# FPGA_DDR3_IO.net
KiCad netlist of a schematic drawn in Altium Designer
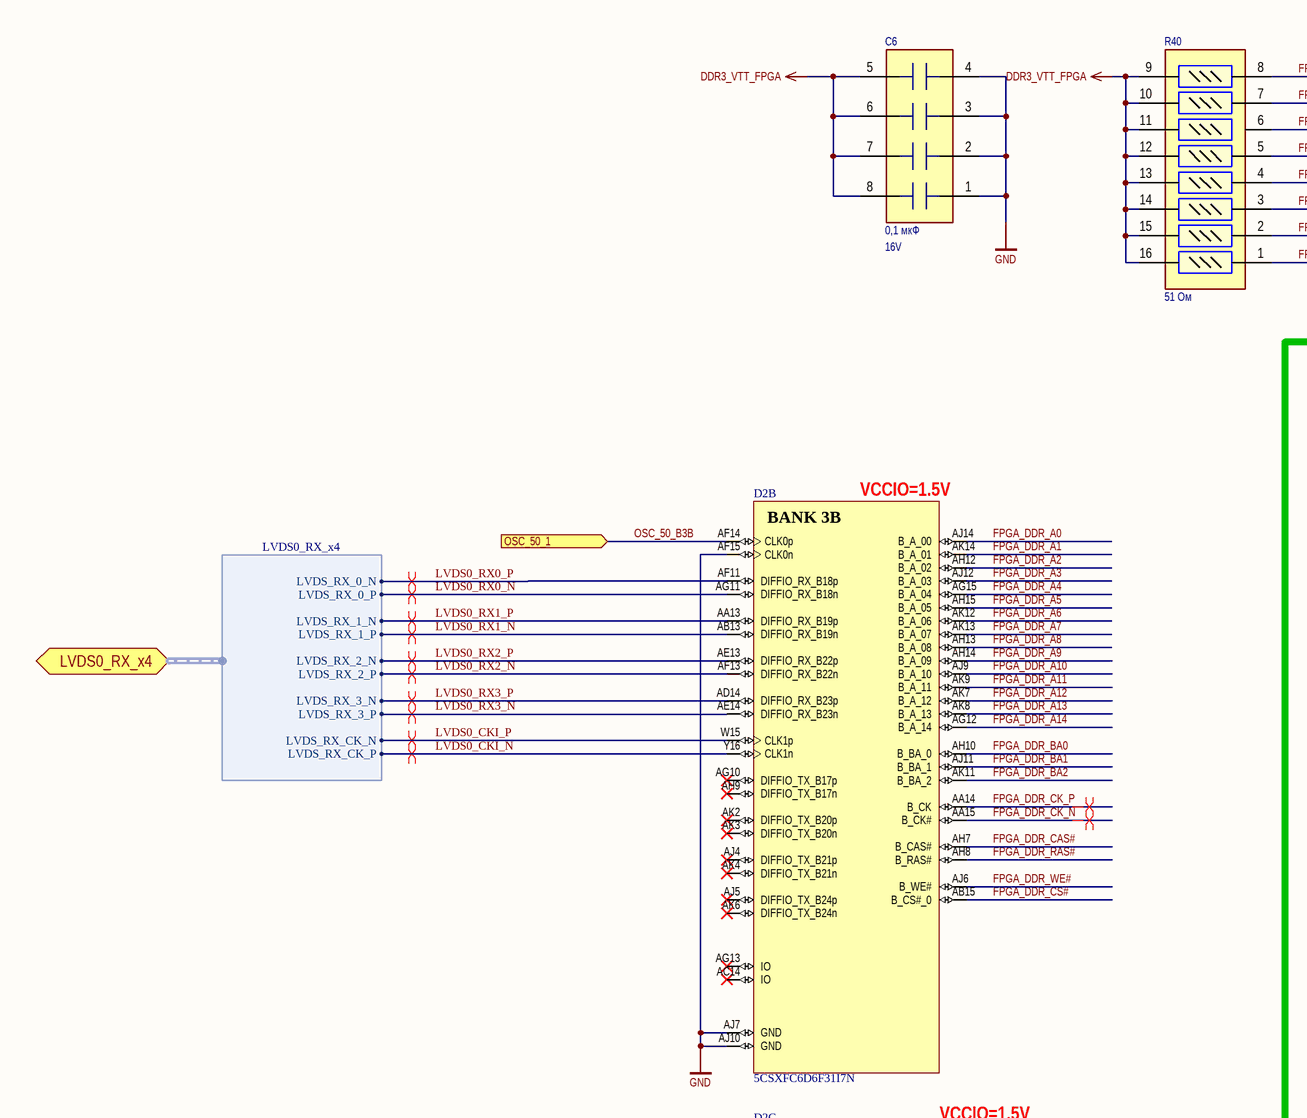
[diagram p0: FPGA_DDR3&IO.SchDoc, top left]
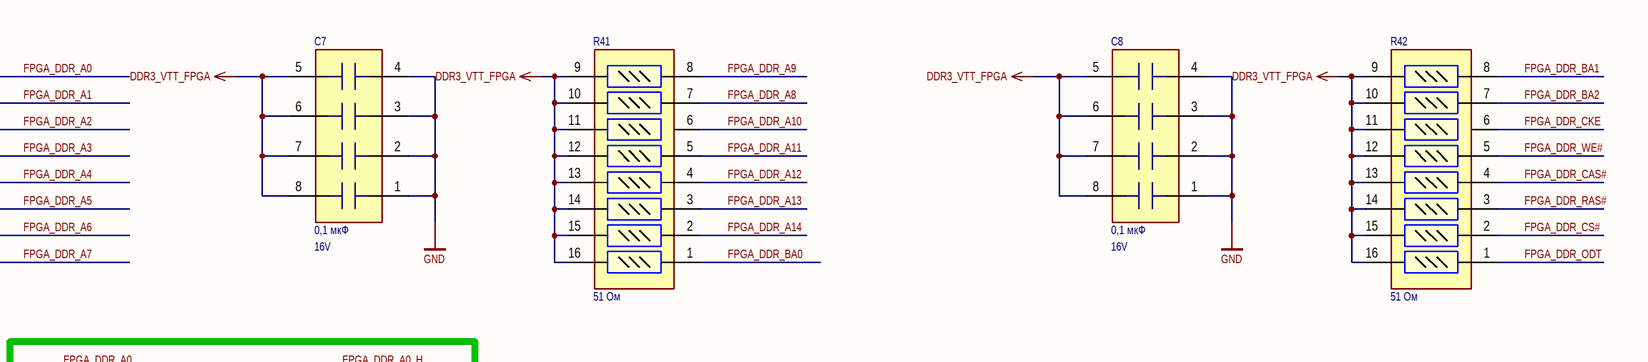
[diagram p1: FPGA_DDR3&IO.SchDoc, top right]
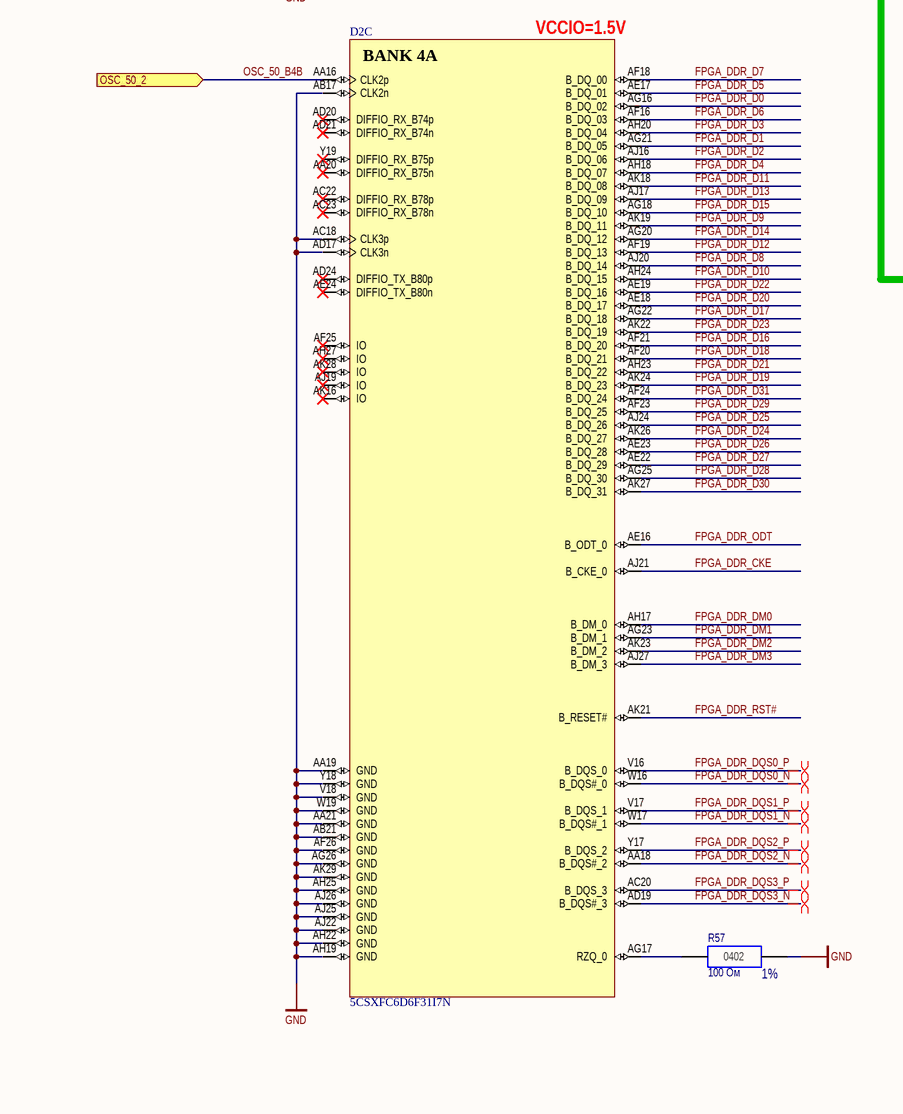
[diagram p2: FPGA_DDR3&IO.SchDoc, bottom left]
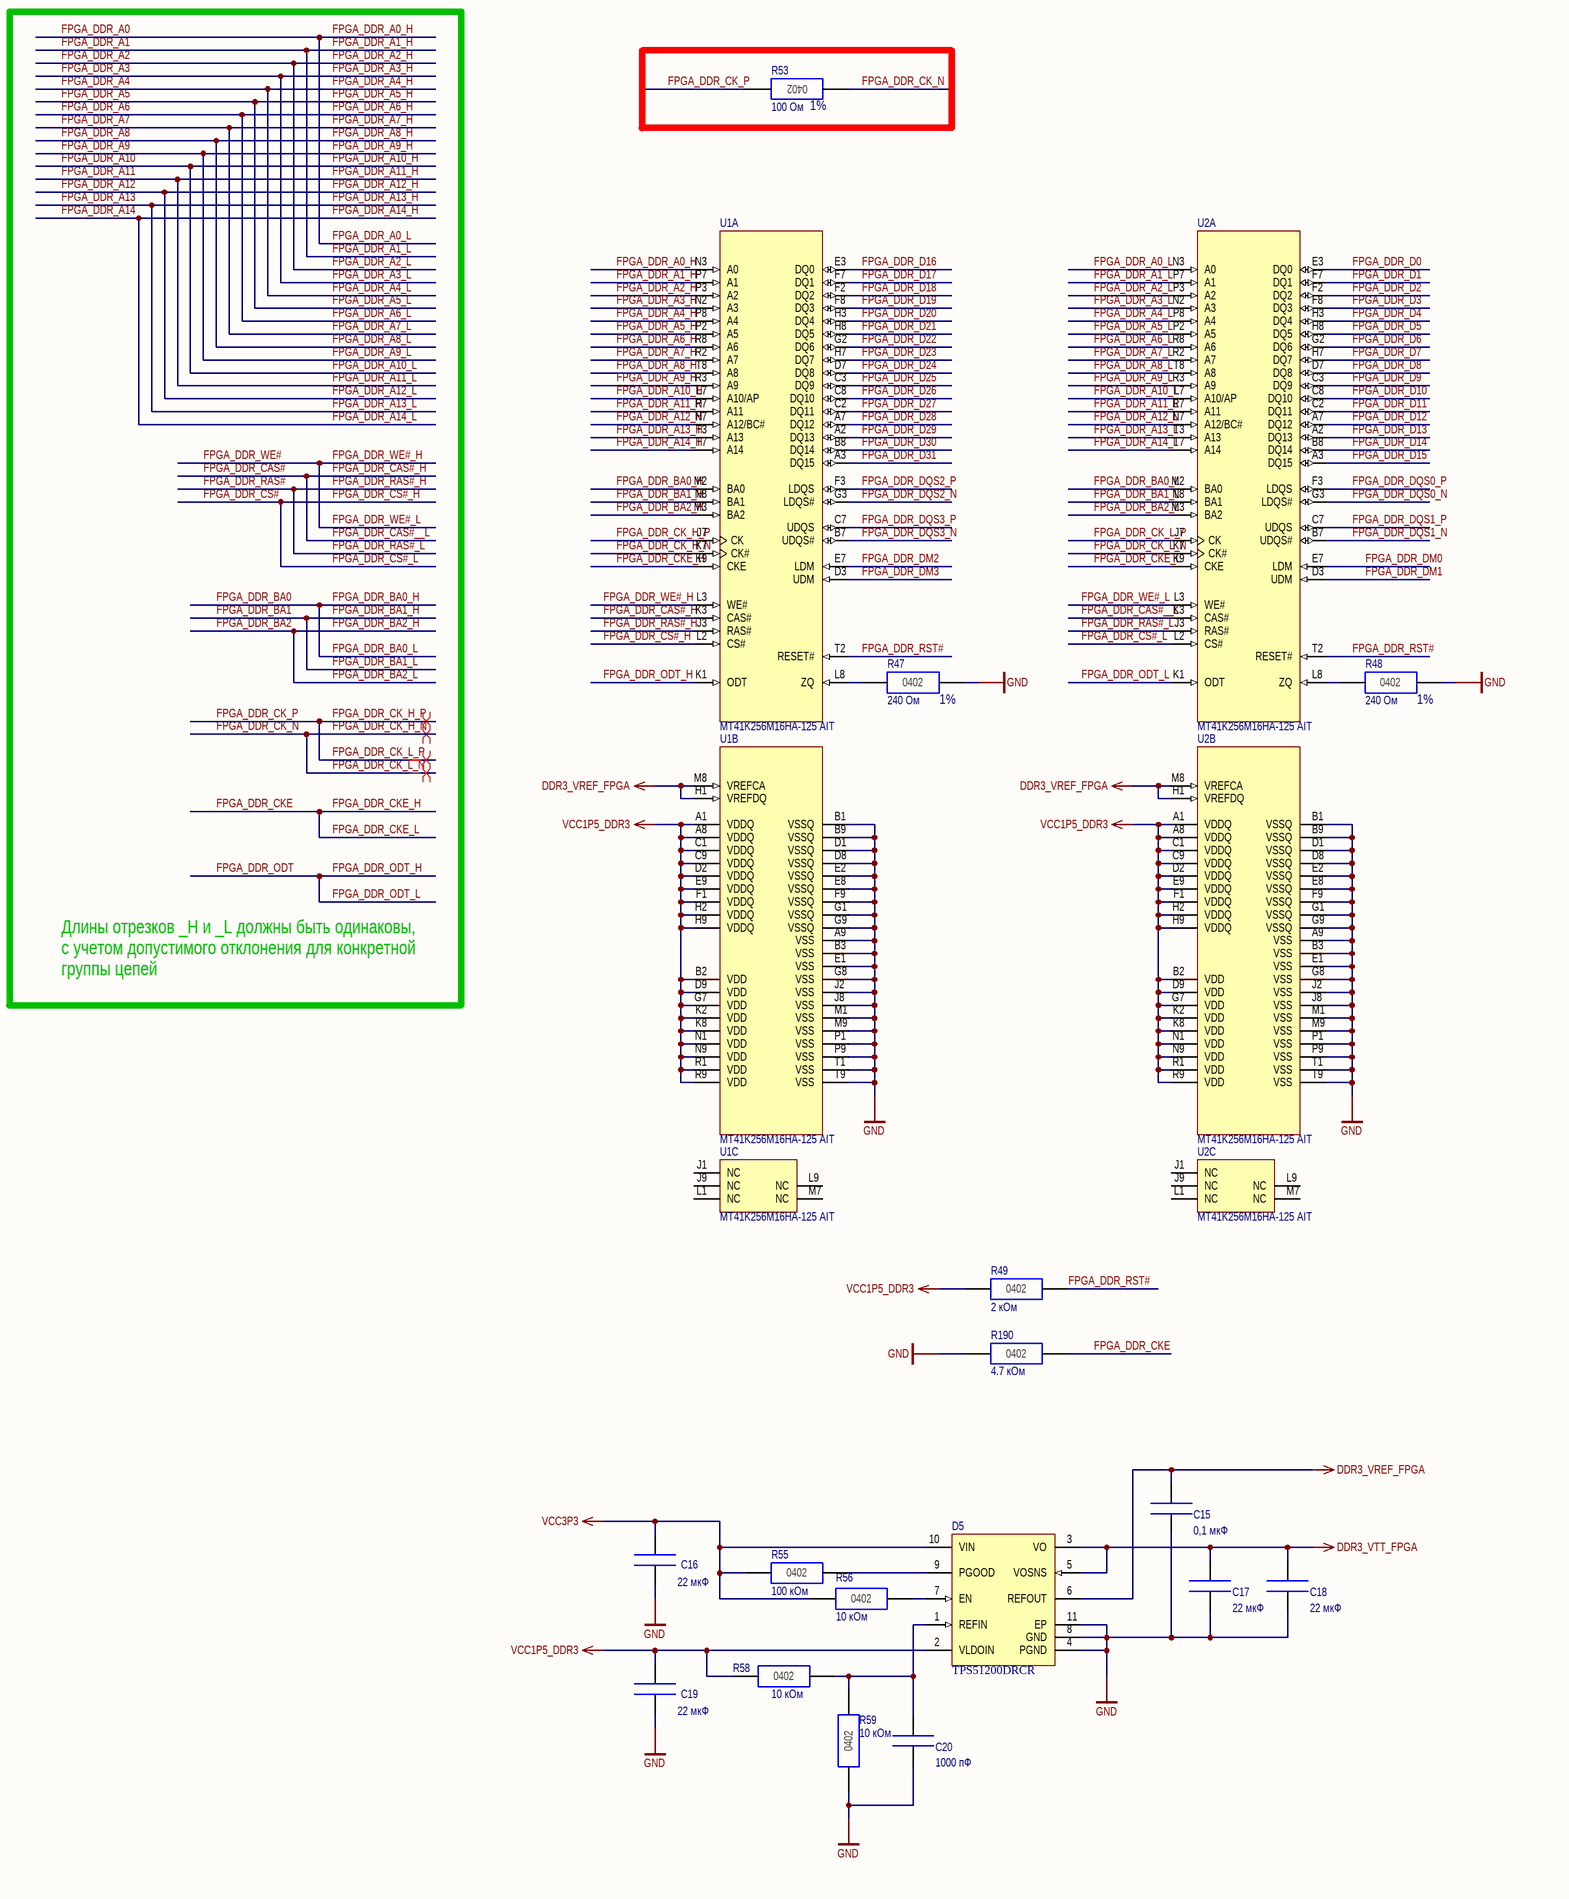
[diagram p3: FPGA_DDR3&IO.SchDoc, bottom right]

(export (version "E")
  (design (tool "Eeschema 10.0.6"))
  (components
    (comp (ref "C6")
      (value "0,1 мкФ")
      (footprint "CAF-80P319X159-8N")
      (description "Чип конденсатор керамический")
      (fields (field (name "V") "16V") (field (name "Comment") "W3A4YC104KAT2A"))
      (libsource (lib "SD_IC") (part "W3A4YC104KAT2A"))
    )
    (comp (ref "C7")
      (value "0,1 мкФ")
      (footprint "CAF-80P319X159-8N")
      (description "Чип конденсатор керамический")
      (fields (field (name "V") "16V") (field (name "Comment") "W3A4YC104KAT2A"))
      (libsource (lib "SD_IC") (part "W3A4YC104KAT2A"))
    )
    (comp (ref "C8")
      (value "0,1 мкФ")
      (footprint "CAF-80P319X159-8N")
      (description "Чип конденсатор керамический")
      (fields (field (name "V") "16V") (field (name "Comment") "W3A4YC104KAT2A"))
      (libsource (lib "SD_IC") (part "W3A4YC104KAT2A"))
    )
    (comp (ref "C15")
      (value "0,1 мкФ")
      (footprint "CC0402(1005)")
      (description "Чип конденсатор керамический")
      (fields (field (name "Comment") "CC0402-X7R-0,1 мкФ-20%-10В"))
      (libsource (lib "Чип конденсаторы") (part "CC0402-X7R-#-20%-10В"))
    )
    (comp (ref "C16")
      (value "22 мкФ")
      (footprint "CC0402(1005)")
      (description "Чип конденсатор керамический")
      (fields (field (name "Comment") "CC0402-X5R-22 мкФ-20%-6.3В"))
      (libsource (lib "Чип конденсаторы") (part "CC0402-X7R-#-20%-10В"))
    )
    (comp (ref "C17")
      (value "22 мкФ")
      (footprint "CC0402(1005)")
      (description "Чип конденсатор керамический")
      (fields (field (name "Comment") "CC0402-X5R-22 мкФ-20%-6.3В"))
      (libsource (lib "Чип конденсаторы") (part "CC0402-X7R-#-20%-10В"))
    )
    (comp (ref "C18")
      (value "22 мкФ")
      (footprint "CC0402(1005)")
      (description "Чип конденсатор керамический")
      (fields (field (name "Comment") "CC0402-X5R-22 мкФ-20%-6.3В"))
      (libsource (lib "Чип конденсаторы") (part "CC0402-X7R-#-20%-10В"))
    )
    (comp (ref "C19")
      (value "22 мкФ")
      (footprint "CC0402(1005)")
      (description "Чип конденсатор керамический")
      (fields (field (name "Comment") "CC0402-X5R-22 мкФ-20%-6.3В"))
      (libsource (lib "Чип конденсаторы") (part "CC0402-X7R-#-20%-10В"))
    )
    (comp (ref "C20")
      (value "1000 пФ")
      (footprint "CC0402(1005)")
      (description "Чип конденсатор керамический")
      (fields (field (name "Comment") "CC0402-NP01000 пФ-1%-50В"))
      (libsource (lib "Чип конденсаторы") (part "CC0402-X7R-#-20%-10В"))
    )
    (comp (ref "D2")
      (value "5CSXFC6D6F31I7N")
      (footprint "ALTR-FBGA896_A-200")
      (fields (field (name "MANUFACTURER") "Altera"))
      (libsource (lib "") (part "5CSXFC6D6F31I7N_1"))
    )
    (comp (ref "D5")
      (value "TPS51200DRCR")
      (footprint "TI-DRC10-2400X1650TP_V")
      (fields (field (name "MANUFACTURER") "Texas Instruments"))
      (libsource (lib "SD_IC") (part "TPS51200DRCR"))
    )
    (comp (ref "R40")
      (value "51 Ом")
      (footprint "YC248")
      (description "Набор чип резисторов")
      (fields (field (name "Comment") "YC248-JR-07-51 Ом"))
      (libsource (lib "SD_IC") (part "YC248-JR-07-#"))
    )
    (comp (ref "R41")
      (value "51 Ом")
      (footprint "VOU_SOM_Vlad:YC248")
      (description "Набор чип резисторов")
      (fields (field (name "Comment") "YC248-JR-07-51 Ом"))
      (libsource (lib "SD_IC") (part "YC248-JR-07-#"))
    )
    (comp (ref "R42")
      (value "51 Ом")
      (footprint "YC248")
      (description "Набор чип резисторов")
      (fields (field (name "Comment") "YC248-JR-07-51 Ом"))
      (libsource (lib "SD_IC") (part "YC248-JR-07-#"))
    )
    (comp (ref "R47")
      (value "240 Ом")
      (footprint "CR0402(1005)")
      (description "Чип резистор")
      (fields (field (name "TOLERANCE") "1%") (field (name "Comment") "CR0402-240 Ом-±TOLERANCE"))
      (libsource (lib "Резисторы") (part "CR0402-#-±5%"))
    )
    (comp (ref "R48")
      (value "240 Ом")
      (footprint "CR0402(1005)")
      (description "Чип резистор")
      (fields (field (name "TOLERANCE") "1%") (field (name "Comment") "CR0402-240 Ом-±TOLERANCE"))
      (libsource (lib "Резисторы") (part "CR0402-#-±5%"))
    )
    (comp (ref "R49")
      (value "2 кОм")
      (footprint "CR0402(1005)")
      (description "Чип резистор")
      (fields (field (name "TOLERANCE") "5%") (field (name "Comment") "CR0402-2 кОм-±5%"))
      (libsource (lib "Резисторы") (part "CR0402-#-±5%"))
    )
    (comp (ref "R53")
      (value "100 Ом")
      (footprint "CR0402(1005)")
      (description "Чип резистор")
      (fields (field (name "TOLERANCE") "1%") (field (name "Comment") "CR0402-100 Ом-±TOLERANCE"))
      (libsource (lib "") (part "CR0402-#-±5%_1"))
    )
    (comp (ref "R55")
      (value "100 кОм")
      (footprint "CR0402(1005)")
      (description "Чип резистор")
      (fields (field (name "TOLERANCE") "5%") (field (name "Comment") "CR0402-100 кОм-±5%"))
      (libsource (lib "Резисторы") (part "CR0402-#-±5%"))
    )
    (comp (ref "R56")
      (value "10 кОм")
      (footprint "CR0402(1005)")
      (description "Чип резистор")
      (fields (field (name "TOLERANCE") "5%") (field (name "Comment") "CR0402-10 кОм-±5%"))
      (libsource (lib "Резисторы") (part "CR0402-#-±5%"))
    )
    (comp (ref "R57")
      (value "100 Ом")
      (footprint "CC0402(1005)_OCT")
      (description "Чип резистор")
      (fields (field (name "TOLERANCE") "1%") (field (name "Comment") "CR0402-100 Ом-±TOLERANCE"))
      (libsource (lib "Резисторы") (part "CR0402-#-±5%"))
    )
    (comp (ref "R58")
      (value "10 кОм")
      (footprint "CR0402(1005)")
      (description "Чип резистор")
      (fields (field (name "TOLERANCE") "5%") (field (name "Comment") "CR0402-10 кОм-±5%"))
      (libsource (lib "Резисторы") (part "CR0402-#-±5%"))
    )
    (comp (ref "R59")
      (value "10 кОм")
      (footprint "CR0402(1005)")
      (description "Чип резистор")
      (fields (field (name "TOLERANCE") "5%") (field (name "Comment") "CR0402-10 кОм-±5%"))
      (libsource (lib "") (part "CR0402-#-±5%_2"))
    )
    (comp (ref "R190")
      (value "4.7 кОм")
      (footprint "CR0402(1005)")
      (description "Чип резистор")
      (fields (field (name "TOLERANCE") "5%") (field (name "Comment") "CR0402-4.7 кОм-±5%"))
      (libsource (lib "Резисторы") (part "CR0402-#-±5%"))
    )
    (comp (ref "U1")
      (value "MT41K256M16HA-125 AIT")
      (footprint "MICT-HA-96")
      (description "4Gb DDR3-1600 SDRAM, 256Mb x 16, 1.25ns, 1.35V, -40 to 95 degC, 96-Ball FBGA, Pb-Free")
      (fields (field (name "VOLTAGE") "1.35V ") (field (name "MANUFACTURER") "Micron"))
      (libsource (lib "SD_IC") (part "MT41K256M16HA-125 AIT"))
    )
    (comp (ref "U2")
      (value "MT41K256M16HA-125 AIT")
      (footprint "MICT-HA-96")
      (description "4Gb DDR3-1600 SDRAM, 256Mb x 16, 1.25ns, 1.35V, -40 to 95 degC, 96-Ball FBGA, Pb-Free")
      (fields (field (name "VOLTAGE") "1.35V ") (field (name "MANUFACTURER") "Micron"))
      (libsource (lib "SD_IC") (part "MT41K256M16HA-125 AIT"))
    )
  )
  (nets
    (net (code "2") (name "/FPGA_DDR_A0") (class "Default")
      (node (ref "D2") (pin "AJ14") (pinfunction "B_A_00_AJ14") (pintype "bidirectional"))
      (node (ref "R40") (pin "8") (pintype "passive"))
      (node (ref "U1") (pin "N3") (pinfunction "A0_N3") (pintype "input"))
      (node (ref "U2") (pin "N3") (pinfunction "A0_N3") (pintype "input"))
    )
    (net (code "3") (name "/FPGA_DDR_A1") (class "Default")
      (node (ref "D2") (pin "AK14") (pinfunction "B_A_01_AK14") (pintype "bidirectional"))
      (node (ref "R40") (pin "7") (pintype "passive"))
      (node (ref "U1") (pin "P7") (pinfunction "A1_P7") (pintype "input"))
      (node (ref "U2") (pin "P7") (pinfunction "A1_P7") (pintype "input"))
    )
    (net (code "4") (name "/FPGA_DDR_A2") (class "Default")
      (node (ref "D2") (pin "AH12") (pinfunction "B_A_02_AH12") (pintype "bidirectional"))
      (node (ref "R40") (pin "6") (pintype "passive"))
      (node (ref "U1") (pin "P3") (pinfunction "A2_P3") (pintype "input"))
      (node (ref "U2") (pin "P3") (pinfunction "A2_P3") (pintype "input"))
    )
    (net (code "5") (name "/FPGA_DDR_A3") (class "Default")
      (node (ref "D2") (pin "AJ12") (pinfunction "B_A_03_AJ12") (pintype "bidirectional"))
      (node (ref "R40") (pin "5") (pintype "passive"))
      (node (ref "U1") (pin "N2") (pinfunction "A3_N2") (pintype "input"))
      (node (ref "U2") (pin "N2") (pinfunction "A3_N2") (pintype "input"))
    )
    (net (code "6") (name "/FPGA_DDR_A4") (class "Default")
      (node (ref "D2") (pin "AG15") (pinfunction "B_A_04_AG15") (pintype "bidirectional"))
      (node (ref "R40") (pin "4") (pintype "passive"))
      (node (ref "U1") (pin "P8") (pinfunction "A4_P8") (pintype "input"))
      (node (ref "U2") (pin "P8") (pinfunction "A4_P8") (pintype "input"))
    )
    (net (code "7") (name "/FPGA_DDR_A5") (class "Default")
      (node (ref "D2") (pin "AH15") (pinfunction "B_A_05_AH15") (pintype "bidirectional"))
      (node (ref "R40") (pin "3") (pintype "passive"))
      (node (ref "U1") (pin "P2") (pinfunction "A5_P2") (pintype "input"))
      (node (ref "U2") (pin "P2") (pinfunction "A5_P2") (pintype "input"))
    )
    (net (code "8") (name "/FPGA_DDR_A6") (class "Default")
      (node (ref "D2") (pin "AK12") (pinfunction "B_A_06_AK12") (pintype "bidirectional"))
      (node (ref "R40") (pin "2") (pintype "passive"))
      (node (ref "U1") (pin "R8") (pinfunction "A6_R8") (pintype "input"))
      (node (ref "U2") (pin "R8") (pinfunction "A6_R8") (pintype "input"))
    )
    (net (code "9") (name "/FPGA_DDR_A7") (class "Default")
      (node (ref "D2") (pin "AK13") (pinfunction "B_A_07_AK13") (pintype "bidirectional"))
      (node (ref "R40") (pin "1") (pintype "passive"))
      (node (ref "U1") (pin "R2") (pinfunction "A7_R2") (pintype "input"))
      (node (ref "U2") (pin "R2") (pinfunction "A7_R2") (pintype "input"))
    )
    (net (code "10") (name "/FPGA_DDR_A8") (class "Default")
      (node (ref "D2") (pin "AH13") (pinfunction "B_A_08_AH13") (pintype "bidirectional"))
      (node (ref "R41") (pin "7") (pintype "passive"))
      (node (ref "U1") (pin "T8") (pinfunction "A8_T8") (pintype "input"))
      (node (ref "U2") (pin "T8") (pinfunction "A8_T8") (pintype "input"))
    )
    (net (code "11") (name "/FPGA_DDR_A9") (class "Default")
      (node (ref "D2") (pin "AH14") (pinfunction "B_A_09_AH14") (pintype "bidirectional"))
      (node (ref "R41") (pin "8") (pintype "passive"))
      (node (ref "U1") (pin "R3") (pinfunction "A9_R3") (pintype "input"))
      (node (ref "U2") (pin "R3") (pinfunction "A9_R3") (pintype "input"))
    )
    (net (code "12") (name "/FPGA_DDR_A10") (class "Default")
      (node (ref "D2") (pin "AJ9") (pinfunction "B_A_10_AJ9") (pintype "bidirectional"))
      (node (ref "R41") (pin "6") (pintype "passive"))
      (node (ref "U1") (pin "L7") (pinfunction "A10/AP_L7") (pintype "input"))
      (node (ref "U2") (pin "L7") (pinfunction "A10/AP_L7") (pintype "input"))
    )
    (net (code "13") (name "/FPGA_DDR_A11") (class "Default")
      (node (ref "D2") (pin "AK9") (pinfunction "B_A_11_AK9") (pintype "bidirectional"))
      (node (ref "R41") (pin "5") (pintype "passive"))
      (node (ref "U1") (pin "R7") (pinfunction "A11_R7") (pintype "input"))
      (node (ref "U2") (pin "R7") (pinfunction "A11_R7") (pintype "input"))
    )
    (net (code "14") (name "/FPGA_DDR_A12") (class "Default")
      (node (ref "D2") (pin "AK7") (pinfunction "B_A_12_AK7") (pintype "bidirectional"))
      (node (ref "R41") (pin "4") (pintype "passive"))
      (node (ref "U1") (pin "N7") (pinfunction "A12/BC#_N7") (pintype "input"))
      (node (ref "U2") (pin "N7") (pinfunction "A12/BC#_N7") (pintype "input"))
    )
    (net (code "15") (name "/FPGA_DDR_A13") (class "Default")
      (node (ref "D2") (pin "AK8") (pinfunction "B_A_13_AK8") (pintype "bidirectional"))
      (node (ref "R41") (pin "3") (pintype "passive"))
      (node (ref "U1") (pin "T3") (pinfunction "A13_T3") (pintype "input"))
      (node (ref "U2") (pin "T3") (pinfunction "A13_T3") (pintype "input"))
    )
    (net (code "16") (name "/FPGA_DDR_A14") (class "Default")
      (node (ref "D2") (pin "AG12") (pinfunction "B_A_14_AG12") (pintype "bidirectional"))
      (node (ref "R41") (pin "2") (pintype "passive"))
      (node (ref "U1") (pin "T7") (pinfunction "A14_T7") (pintype "input"))
      (node (ref "U2") (pin "T7") (pinfunction "A14_T7") (pintype "input"))
    )
    (net (code "17") (name "/FPGA_DDR_BA0") (class "Default")
      (node (ref "D2") (pin "AH10") (pinfunction "B_BA_0_AH10") (pintype "bidirectional"))
      (node (ref "R41") (pin "1") (pintype "passive"))
      (node (ref "U1") (pin "M2") (pinfunction "BA0_M2") (pintype "input"))
      (node (ref "U2") (pin "M2") (pinfunction "BA0_M2") (pintype "input"))
    )
    (net (code "18") (name "/FPGA_DDR_BA1") (class "Default")
      (node (ref "D2") (pin "AJ11") (pinfunction "B_BA_1_AJ11") (pintype "bidirectional"))
      (node (ref "R42") (pin "8") (pintype "passive"))
      (node (ref "U1") (pin "N8") (pinfunction "BA1_N8") (pintype "input"))
      (node (ref "U2") (pin "N8") (pinfunction "BA1_N8") (pintype "input"))
    )
    (net (code "19") (name "/FPGA_DDR_BA2") (class "Default")
      (node (ref "D2") (pin "AK11") (pinfunction "B_BA_2_AK11") (pintype "bidirectional"))
      (node (ref "R42") (pin "7") (pintype "passive"))
      (node (ref "U1") (pin "M3") (pinfunction "BA2_M3") (pintype "input"))
      (node (ref "U2") (pin "M3") (pinfunction "BA2_M3") (pintype "input"))
    )
    (net (code "20") (name "/FPGA_DDR_CAS#") (class "Default")
      (node (ref "D2") (pin "AH7") (pinfunction "B_CAS#_AH7") (pintype "bidirectional"))
      (node (ref "R42") (pin "4") (pintype "passive"))
      (node (ref "U1") (pin "K3") (pinfunction "CAS#_K3") (pintype "input"))
      (node (ref "U2") (pin "K3") (pinfunction "CAS#_K3") (pintype "input"))
    )
    (net (code "21") (name "/FPGA_DDR_CKE") (class "Default")
      (node (ref "D2") (pin "AJ21") (pinfunction "B_CKE_0_AJ21") (pintype "bidirectional"))
      (node (ref "R190") (pin "2") (pinfunction "-_2") (pintype "passive"))
      (node (ref "R42") (pin "6") (pintype "passive"))
      (node (ref "U1") (pin "K9") (pinfunction "CKE_K9") (pintype "input"))
      (node (ref "U2") (pin "K9") (pinfunction "CKE_K9") (pintype "input"))
    )
    (net (code "22") (name "/FPGA_DDR_CK_H_N") (class "Default")
      (node (ref "D2") (pin "AA15") (pinfunction "B_CK#_AA15") (pintype "bidirectional"))
      (node (ref "R53") (pin "1") (pinfunction "+_1") (pintype "passive"))
      (node (ref "U1") (pin "K7") (pinfunction "CK#_K7") (pintype "input"))
      (node (ref "U2") (pin "K7") (pinfunction "CK#_K7") (pintype "input"))
    )
    (net (code "23") (name "/FPGA_DDR_CK_H_P") (class "Default")
      (node (ref "D2") (pin "AA14") (pinfunction "B_CK_AA14") (pintype "bidirectional"))
      (node (ref "R53") (pin "2") (pinfunction "-_2") (pintype "passive"))
      (node (ref "U1") (pin "J7") (pinfunction "CK_J7") (pintype "input"))
      (node (ref "U2") (pin "J7") (pinfunction "CK_J7") (pintype "input"))
    )
    (net (code "24") (name "/FPGA_DDR_CS#") (class "Default")
      (node (ref "D2") (pin "AB15") (pinfunction "B_CS#_0_AB15") (pintype "bidirectional"))
      (node (ref "R42") (pin "2") (pintype "passive"))
      (node (ref "U1") (pin "L2") (pinfunction "CS#_L2") (pintype "input"))
      (node (ref "U2") (pin "L2") (pinfunction "CS#_L2") (pintype "input"))
    )
    (net (code "25") (name "/FPGA_DDR_D0") (class "Default")
      (node (ref "D2") (pin "AG16") (pinfunction "B_DQ_02_AG16") (pintype "bidirectional"))
      (node (ref "U2") (pin "E3") (pinfunction "DQ0_E3") (pintype "bidirectional"))
    )
    (net (code "26") (name "/FPGA_DDR_D1") (class "Default")
      (node (ref "D2") (pin "AG21") (pinfunction "B_DQ_05_AG21") (pintype "bidirectional"))
      (node (ref "U2") (pin "F7") (pinfunction "DQ1_F7") (pintype "bidirectional"))
    )
    (net (code "27") (name "/FPGA_DDR_D2") (class "Default")
      (node (ref "D2") (pin "AJ16") (pinfunction "B_DQ_06_AJ16") (pintype "bidirectional"))
      (node (ref "U2") (pin "F2") (pinfunction "DQ2_F2") (pintype "bidirectional"))
    )
    (net (code "28") (name "/FPGA_DDR_D3") (class "Default")
      (node (ref "D2") (pin "AH20") (pinfunction "B_DQ_04_AH20") (pintype "bidirectional"))
      (node (ref "U2") (pin "F8") (pinfunction "DQ3_F8") (pintype "bidirectional"))
    )
    (net (code "29") (name "/FPGA_DDR_D4") (class "Default")
      (node (ref "D2") (pin "AH18") (pinfunction "B_DQ_07_AH18") (pintype "bidirectional"))
      (node (ref "U2") (pin "H3") (pinfunction "DQ4_H3") (pintype "bidirectional"))
    )
    (net (code "30") (name "/FPGA_DDR_D5") (class "Default")
      (node (ref "D2") (pin "AE17") (pinfunction "B_DQ_01_AE17") (pintype "bidirectional"))
      (node (ref "U2") (pin "H8") (pinfunction "DQ5_H8") (pintype "bidirectional"))
    )
    (net (code "31") (name "/FPGA_DDR_D6") (class "Default")
      (node (ref "D2") (pin "AF16") (pinfunction "B_DQ_03_AF16") (pintype "bidirectional"))
      (node (ref "U2") (pin "G2") (pinfunction "DQ6_G2") (pintype "bidirectional"))
    )
    (net (code "32") (name "/FPGA_DDR_D7") (class "Default")
      (node (ref "D2") (pin "AF18") (pinfunction "B_DQ_00_AF18") (pintype "bidirectional"))
      (node (ref "U2") (pin "H7") (pinfunction "DQ7_H7") (pintype "bidirectional"))
    )
    (net (code "33") (name "/FPGA_DDR_D8") (class "Default")
      (node (ref "D2") (pin "AJ20") (pinfunction "B_DQ_14_AJ20") (pintype "bidirectional"))
      (node (ref "U2") (pin "D7") (pinfunction "DQ8_D7") (pintype "bidirectional"))
    )
    (net (code "34") (name "/FPGA_DDR_D9") (class "Default")
      (node (ref "D2") (pin "AK19") (pinfunction "B_DQ_11_AK19") (pintype "bidirectional"))
      (node (ref "U2") (pin "C3") (pinfunction "DQ9_C3") (pintype "bidirectional"))
    )
    (net (code "35") (name "/FPGA_DDR_D10") (class "Default")
      (node (ref "D2") (pin "AH24") (pinfunction "B_DQ_15_AH24") (pintype "bidirectional"))
      (node (ref "U2") (pin "C8") (pinfunction "DQ10_C8") (pintype "bidirectional"))
    )
    (net (code "36") (name "/FPGA_DDR_D11") (class "Default")
      (node (ref "D2") (pin "AK18") (pinfunction "B_DQ_08_AK18") (pintype "bidirectional"))
      (node (ref "U2") (pin "C2") (pinfunction "DQ11_C2") (pintype "bidirectional"))
    )
    (net (code "37") (name "/FPGA_DDR_D12") (class "Default")
      (node (ref "D2") (pin "AF19") (pinfunction "B_DQ_13_AF19") (pintype "bidirectional"))
      (node (ref "U2") (pin "A7") (pinfunction "DQ12_A7") (pintype "bidirectional"))
    )
    (net (code "38") (name "/FPGA_DDR_D13") (class "Default")
      (node (ref "D2") (pin "AJ17") (pinfunction "B_DQ_09_AJ17") (pintype "bidirectional"))
      (node (ref "U2") (pin "A2") (pinfunction "DQ13_A2") (pintype "bidirectional"))
    )
    (net (code "39") (name "/FPGA_DDR_D14") (class "Default")
      (node (ref "D2") (pin "AG20") (pinfunction "B_DQ_12_AG20") (pintype "bidirectional"))
      (node (ref "U2") (pin "B8") (pinfunction "DQ14_B8") (pintype "bidirectional"))
    )
    (net (code "40") (name "/FPGA_DDR_D15") (class "Default")
      (node (ref "D2") (pin "AG18") (pinfunction "B_DQ_10_AG18") (pintype "bidirectional"))
      (node (ref "U2") (pin "A3") (pinfunction "DQ15_A3") (pintype "bidirectional"))
    )
    (net (code "41") (name "/FPGA_DDR_D16") (class "Default")
      (node (ref "D2") (pin "AF21") (pinfunction "B_DQ_20_AF21") (pintype "bidirectional"))
      (node (ref "U1") (pin "E3") (pinfunction "DQ0_E3") (pintype "bidirectional"))
    )
    (net (code "42") (name "/FPGA_DDR_D17") (class "Default")
      (node (ref "D2") (pin "AG22") (pinfunction "B_DQ_18_AG22") (pintype "bidirectional"))
      (node (ref "U1") (pin "F7") (pinfunction "DQ1_F7") (pintype "bidirectional"))
    )
    (net (code "43") (name "/FPGA_DDR_D18") (class "Default")
      (node (ref "D2") (pin "AF20") (pinfunction "B_DQ_21_AF20") (pintype "bidirectional"))
      (node (ref "U1") (pin "F2") (pinfunction "DQ2_F2") (pintype "bidirectional"))
    )
    (net (code "44") (name "/FPGA_DDR_D19") (class "Default")
      (node (ref "D2") (pin "AK24") (pinfunction "B_DQ_23_AK24") (pintype "bidirectional"))
      (node (ref "U1") (pin "F8") (pinfunction "DQ3_F8") (pintype "bidirectional"))
    )
    (net (code "45") (name "/FPGA_DDR_D20") (class "Default")
      (node (ref "D2") (pin "AE18") (pinfunction "B_DQ_17_AE18") (pintype "bidirectional"))
      (node (ref "U1") (pin "H3") (pinfunction "DQ4_H3") (pintype "bidirectional"))
    )
    (net (code "46") (name "/FPGA_DDR_D21") (class "Default")
      (node (ref "D2") (pin "AH23") (pinfunction "B_DQ_22_AH23") (pintype "bidirectional"))
      (node (ref "U1") (pin "H8") (pinfunction "DQ5_H8") (pintype "bidirectional"))
    )
    (net (code "47") (name "/FPGA_DDR_D22") (class "Default")
      (node (ref "D2") (pin "AE19") (pinfunction "B_DQ_16_AE19") (pintype "bidirectional"))
      (node (ref "U1") (pin "G2") (pinfunction "DQ6_G2") (pintype "bidirectional"))
    )
    (net (code "48") (name "/FPGA_DDR_D23") (class "Default")
      (node (ref "D2") (pin "AK22") (pinfunction "B_DQ_19_AK22") (pintype "bidirectional"))
      (node (ref "U1") (pin "H7") (pinfunction "DQ7_H7") (pintype "bidirectional"))
    )
    (net (code "49") (name "/FPGA_DDR_D24") (class "Default")
      (node (ref "D2") (pin "AK26") (pinfunction "B_DQ_27_AK26") (pintype "bidirectional"))
      (node (ref "U1") (pin "D7") (pinfunction "DQ8_D7") (pintype "bidirectional"))
    )
    (net (code "50") (name "/FPGA_DDR_D25") (class "Default")
      (node (ref "D2") (pin "AJ24") (pinfunction "B_DQ_26_AJ24") (pintype "bidirectional"))
      (node (ref "U1") (pin "C3") (pinfunction "DQ9_C3") (pintype "bidirectional"))
    )
    (net (code "51") (name "/FPGA_DDR_D26") (class "Default")
      (node (ref "D2") (pin "AE23") (pinfunction "B_DQ_28_AE23") (pintype "bidirectional"))
      (node (ref "U1") (pin "C8") (pinfunction "DQ10_C8") (pintype "bidirectional"))
    )
    (net (code "52") (name "/FPGA_DDR_D27") (class "Default")
      (node (ref "D2") (pin "AE22") (pinfunction "B_DQ_29_AE22") (pintype "bidirectional"))
      (node (ref "U1") (pin "C2") (pinfunction "DQ11_C2") (pintype "bidirectional"))
    )
    (net (code "53") (name "/FPGA_DDR_D28") (class "Default")
      (node (ref "D2") (pin "AG25") (pinfunction "B_DQ_30_AG25") (pintype "bidirectional"))
      (node (ref "U1") (pin "A7") (pinfunction "DQ12_A7") (pintype "bidirectional"))
    )
    (net (code "54") (name "/FPGA_DDR_D29") (class "Default")
      (node (ref "D2") (pin "AF23") (pinfunction "B_DQ_25_AF23") (pintype "bidirectional"))
      (node (ref "U1") (pin "A2") (pinfunction "DQ13_A2") (pintype "bidirectional"))
    )
    (net (code "55") (name "/FPGA_DDR_D30") (class "Default")
      (node (ref "D2") (pin "AK27") (pinfunction "B_DQ_31_AK27") (pintype "bidirectional"))
      (node (ref "U1") (pin "B8") (pinfunction "DQ14_B8") (pintype "bidirectional"))
    )
    (net (code "56") (name "/FPGA_DDR_D31") (class "Default")
      (node (ref "D2") (pin "AF24") (pinfunction "B_DQ_24_AF24") (pintype "bidirectional"))
      (node (ref "U1") (pin "A3") (pinfunction "DQ15_A3") (pintype "bidirectional"))
    )
    (net (code "57") (name "/FPGA_DDR_DM0") (class "Default")
      (node (ref "D2") (pin "AH17") (pinfunction "B_DM_0_AH17") (pintype "bidirectional"))
      (node (ref "U2") (pin "E7") (pinfunction "LDM_E7") (pintype "input"))
    )
    (net (code "58") (name "/FPGA_DDR_DM1") (class "Default")
      (node (ref "D2") (pin "AG23") (pinfunction "B_DM_1_AG23") (pintype "bidirectional"))
      (node (ref "U2") (pin "D3") (pinfunction "UDM_D3") (pintype "input"))
    )
    (net (code "59") (name "/FPGA_DDR_DM2") (class "Default")
      (node (ref "D2") (pin "AK23") (pinfunction "B_DM_2_AK23") (pintype "bidirectional"))
      (node (ref "U1") (pin "E7") (pinfunction "LDM_E7") (pintype "input"))
    )
    (net (code "60") (name "/FPGA_DDR_DM3") (class "Default")
      (node (ref "D2") (pin "AJ27") (pinfunction "B_DM_3_AJ27") (pintype "bidirectional"))
      (node (ref "U1") (pin "D3") (pinfunction "UDM_D3") (pintype "input"))
    )
    (net (code "61") (name "/FPGA_DDR_DQS0_N") (class "Default")
      (node (ref "D2") (pin "W16") (pinfunction "B_DQS#_0_W16") (pintype "bidirectional"))
      (node (ref "U2") (pin "G3") (pinfunction "LDQS#_G3") (pintype "bidirectional"))
    )
    (net (code "62") (name "/FPGA_DDR_DQS0_P") (class "Default")
      (node (ref "D2") (pin "V16") (pinfunction "B_DQS_0_V16") (pintype "bidirectional"))
      (node (ref "U2") (pin "F3") (pinfunction "LDQS_F3") (pintype "bidirectional"))
    )
    (net (code "63") (name "/FPGA_DDR_DQS1_N") (class "Default")
      (node (ref "D2") (pin "W17") (pinfunction "B_DQS#_1_W17") (pintype "bidirectional"))
      (node (ref "U2") (pin "B7") (pinfunction "UDQS#_B7") (pintype "bidirectional"))
    )
    (net (code "64") (name "/FPGA_DDR_DQS1_P") (class "Default")
      (node (ref "D2") (pin "V17") (pinfunction "B_DQS_1_V17") (pintype "bidirectional"))
      (node (ref "U2") (pin "C7") (pinfunction "UDQS_C7") (pintype "bidirectional"))
    )
    (net (code "65") (name "/FPGA_DDR_DQS2_N") (class "Default")
      (node (ref "D2") (pin "AA18") (pinfunction "B_DQS#_2_AA18") (pintype "bidirectional"))
      (node (ref "U1") (pin "G3") (pinfunction "LDQS#_G3") (pintype "bidirectional"))
    )
    (net (code "66") (name "/FPGA_DDR_DQS2_P") (class "Default")
      (node (ref "D2") (pin "Y17") (pinfunction "B_DQS_2_Y17") (pintype "bidirectional"))
      (node (ref "U1") (pin "F3") (pinfunction "LDQS_F3") (pintype "bidirectional"))
    )
    (net (code "67") (name "/FPGA_DDR_DQS3_N") (class "Default")
      (node (ref "D2") (pin "AD19") (pinfunction "B_DQS#_3_AD19") (pintype "bidirectional"))
      (node (ref "U1") (pin "B7") (pinfunction "UDQS#_B7") (pintype "bidirectional"))
    )
    (net (code "68") (name "/FPGA_DDR_DQS3_P") (class "Default")
      (node (ref "D2") (pin "AC20") (pinfunction "B_DQS_3_AC20") (pintype "bidirectional"))
      (node (ref "U1") (pin "C7") (pinfunction "UDQS_C7") (pintype "bidirectional"))
    )
    (net (code "69") (name "/FPGA_DDR_ODT") (class "Default")
      (node (ref "D2") (pin "AE16") (pinfunction "B_ODT_0_AE16") (pintype "bidirectional"))
      (node (ref "R42") (pin "1") (pintype "passive"))
      (node (ref "U1") (pin "K1") (pinfunction "ODT_K1") (pintype "input"))
      (node (ref "U2") (pin "K1") (pinfunction "ODT_K1") (pintype "input"))
    )
    (net (code "70") (name "/FPGA_DDR_RAS#") (class "Default")
      (node (ref "D2") (pin "AH8") (pinfunction "B_RAS#_AH8") (pintype "bidirectional"))
      (node (ref "R42") (pin "3") (pintype "passive"))
      (node (ref "U1") (pin "J3") (pinfunction "RAS#_J3") (pintype "input"))
      (node (ref "U2") (pin "J3") (pinfunction "RAS#_J3") (pintype "input"))
    )
    (net (code "71") (name "/FPGA_DDR_RST#") (class "Default")
      (node (ref "D2") (pin "AK21") (pinfunction "B_RESET#_AK21") (pintype "bidirectional"))
      (node (ref "R49") (pin "2") (pinfunction "-_2") (pintype "passive"))
      (node (ref "U1") (pin "T2") (pinfunction "RESET#_T2") (pintype "input"))
      (node (ref "U2") (pin "T2") (pinfunction "RESET#_T2") (pintype "input"))
    )
    (net (code "72") (name "/FPGA_DDR_WE#") (class "Default")
      (node (ref "D2") (pin "AJ6") (pinfunction "B_WE#_AJ6") (pintype "bidirectional"))
      (node (ref "R42") (pin "5") (pintype "passive"))
      (node (ref "U1") (pin "L3") (pinfunction "WE#_L3") (pintype "input"))
      (node (ref "U2") (pin "L3") (pinfunction "WE#_L3") (pintype "input"))
    )
    (net (code "74") (name "/LVDS0_CKI_P") (class "Default")
      (node (ref "D2") (pin "W15") (pinfunction "CLK1p_W15") (pintype "bidirectional"))
    )
    (net (code "76") (name "/LVDS0_RX0_P") (class "Default")
      (node (ref "D2") (pin "AF11") (pinfunction "DIFFIO_RX_B18p_AF11") (pintype "bidirectional"))
    )
    (net (code "77") (name "/LVDS0_RX1_N") (class "Default")
      (node (ref "D2") (pin "AB13") (pinfunction "DIFFIO_RX_B19n_AB13") (pintype "bidirectional"))
    )
    (net (code "78") (name "/LVDS0_RX1_P") (class "Default")
      (node (ref "D2") (pin "AA13") (pinfunction "DIFFIO_RX_B19p_AA13") (pintype "bidirectional"))
    )
    (net (code "79") (name "/LVDS0_RX2_N") (class "Default")
      (node (ref "D2") (pin "AF13") (pinfunction "DIFFIO_RX_B22n_AF13") (pintype "bidirectional"))
    )
    (net (code "80") (name "/LVDS0_RX2_P") (class "Default")
      (node (ref "D2") (pin "AE13") (pinfunction "DIFFIO_RX_B22p_AE13") (pintype "bidirectional"))
    )
    (net (code "82") (name "/LVDS0_RX3_N") (class "Default")
      (node (ref "D2") (pin "AE14") (pinfunction "DIFFIO_RX_B23n_AE14") (pintype "bidirectional"))
    )
    (net (code "83") (name "/LVDS0_RX3_P") (class "Default")
      (node (ref "D2") (pin "AD14") (pinfunction "DIFFIO_RX_B23p_AD14") (pintype "bidirectional"))
    )
    (net (code "84") (name "/OSC_50_B3B") (class "Default")
      (node (ref "D2") (pin "AF14") (pinfunction "CLK0p_AF14") (pintype "bidirectional"))
    )
    (net (code "86") (name "/OSC_50_B4B") (class "Default")
      (node (ref "D2") (pin "AA16") (pinfunction "CLK2p_AA16") (pintype "bidirectional"))
    )
    (net (code "87") (name "DDR3_VREF_FPGA") (class "Default")
      (node (ref "C15") (pin "1") (pinfunction "+_1") (pintype "passive"))
      (node (ref "D5") (pin "6") (pinfunction "REFOUT_6") (pintype "power_in"))
      (node (ref "U1") (pin "H1") (pinfunction "VREFDQ_H1") (pintype "input"))
      (node (ref "U1") (pin "M8") (pinfunction "VREFCA_M8") (pintype "input"))
      (node (ref "U2") (pin "H1") (pinfunction "VREFDQ_H1") (pintype "input"))
      (node (ref "U2") (pin "M8") (pinfunction "VREFCA_M8") (pintype "input"))
    )
    (net (code "88") (name "DDR3_VTT_FPGA") (class "Default")
      (node (ref "C17") (pin "1") (pinfunction "+_1") (pintype "passive"))
      (node (ref "C18") (pin "1") (pinfunction "+_1") (pintype "passive"))
      (node (ref "C6") (pin "5") (pintype "passive"))
      (node (ref "C6") (pin "6") (pintype "passive"))
      (node (ref "C6") (pin "7") (pintype "passive"))
      (node (ref "C6") (pin "8") (pintype "passive"))
      (node (ref "C7") (pin "5") (pintype "passive"))
      (node (ref "C7") (pin "6") (pintype "passive"))
      (node (ref "C7") (pin "7") (pintype "passive"))
      (node (ref "C7") (pin "8") (pintype "passive"))
      (node (ref "C8") (pin "5") (pintype "passive"))
      (node (ref "C8") (pin "6") (pintype "passive"))
      (node (ref "C8") (pin "7") (pintype "passive"))
      (node (ref "C8") (pin "8") (pintype "passive"))
      (node (ref "D5") (pin "3") (pinfunction "VO_3") (pintype "power_in"))
      (node (ref "D5") (pin "5") (pinfunction "VOSNS_5") (pintype "input"))
      (node (ref "R40") (pin "10") (pintype "passive"))
      (node (ref "R40") (pin "11") (pintype "passive"))
      (node (ref "R40") (pin "12") (pintype "passive"))
      (node (ref "R40") (pin "13") (pintype "passive"))
      (node (ref "R40") (pin "14") (pintype "passive"))
      (node (ref "R40") (pin "15") (pintype "passive"))
      (node (ref "R40") (pin "16") (pintype "passive"))
      (node (ref "R40") (pin "9") (pintype "passive"))
      (node (ref "R41") (pin "10") (pintype "passive"))
      (node (ref "R41") (pin "11") (pintype "passive"))
      (node (ref "R41") (pin "12") (pintype "passive"))
      (node (ref "R41") (pin "13") (pintype "passive"))
      (node (ref "R41") (pin "14") (pintype "passive"))
      (node (ref "R41") (pin "15") (pintype "passive"))
      (node (ref "R41") (pin "16") (pintype "passive"))
      (node (ref "R41") (pin "9") (pintype "passive"))
      (node (ref "R42") (pin "10") (pintype "passive"))
      (node (ref "R42") (pin "11") (pintype "passive"))
      (node (ref "R42") (pin "12") (pintype "passive"))
      (node (ref "R42") (pin "13") (pintype "passive"))
      (node (ref "R42") (pin "14") (pintype "passive"))
      (node (ref "R42") (pin "15") (pintype "passive"))
      (node (ref "R42") (pin "16") (pintype "passive"))
      (node (ref "R42") (pin "9") (pintype "passive"))
    )
    (net (code "89") (name "GND") (class "Default")
      (node (ref "C15") (pin "2") (pinfunction "-_2") (pintype "passive"))
      (node (ref "C16") (pin "2") (pinfunction "-_2") (pintype "passive"))
      (node (ref "C17") (pin "2") (pinfunction "-_2") (pintype "passive"))
      (node (ref "C18") (pin "2") (pinfunction "-_2") (pintype "passive"))
      (node (ref "C19") (pin "2") (pinfunction "-_2") (pintype "passive"))
      (node (ref "C20") (pin "2") (pinfunction "-_2") (pintype "passive"))
      (node (ref "C6") (pin "1") (pintype "passive"))
      (node (ref "C6") (pin "2") (pintype "passive"))
      (node (ref "C6") (pin "3") (pintype "passive"))
      (node (ref "C6") (pin "4") (pintype "passive"))
      (node (ref "C7") (pin "1") (pintype "passive"))
      (node (ref "C7") (pin "2") (pintype "passive"))
      (node (ref "C7") (pin "3") (pintype "passive"))
      (node (ref "C7") (pin "4") (pintype "passive"))
      (node (ref "C8") (pin "1") (pintype "passive"))
      (node (ref "C8") (pin "2") (pintype "passive"))
      (node (ref "C8") (pin "3") (pintype "passive"))
      (node (ref "C8") (pin "4") (pintype "passive"))
      (node (ref "D2") (pin "AF15") (pinfunction "CLK0n_AF15") (pintype "bidirectional"))
      (node (ref "D2") (pin "AJ10") (pinfunction "GND_AJ10") (pintype "bidirectional"))
      (node (ref "D2") (pin "AJ22") (pinfunction "GND_AJ22") (pintype "bidirectional"))
      (node (ref "D2") (pin "AJ7") (pinfunction "GND_AJ7") (pintype "bidirectional"))
      (node (ref "D5") (pin "11") (pinfunction "EP_11") (pintype "power_in"))
      (node (ref "D5") (pin "4") (pinfunction "PGND_4") (pintype "power_in"))
      (node (ref "D5") (pin "8") (pinfunction "GND_8") (pintype "power_in"))
      (node (ref "R190") (pin "1") (pinfunction "+_1") (pintype "passive"))
      (node (ref "R47") (pin "2") (pinfunction "-_2") (pintype "passive"))
      (node (ref "R48") (pin "2") (pinfunction "-_2") (pintype "passive"))
      (node (ref "R57") (pin "2") (pinfunction "-_2") (pintype "passive"))
      (node (ref "R59") (pin "1") (pinfunction "+_1") (pintype "passive"))
      (node (ref "U1") (pin "A9") (pinfunction "VSS_A9") (pintype "power_in"))
      (node (ref "U1") (pin "B1") (pinfunction "VSSQ_B1") (pintype "power_in"))
      (node (ref "U1") (pin "B3") (pinfunction "VSS_B3") (pintype "power_in"))
      (node (ref "U1") (pin "B9") (pinfunction "VSSQ_B9") (pintype "power_in"))
      (node (ref "U1") (pin "D1") (pinfunction "VSSQ_D1") (pintype "power_in"))
      (node (ref "U1") (pin "D8") (pinfunction "VSSQ_D8") (pintype "power_in"))
      (node (ref "U1") (pin "E1") (pinfunction "VSS_E1") (pintype "power_in"))
      (node (ref "U1") (pin "E2") (pinfunction "VSSQ_E2") (pintype "power_in"))
      (node (ref "U1") (pin "E8") (pinfunction "VSSQ_E8") (pintype "power_in"))
      (node (ref "U1") (pin "F9") (pinfunction "VSSQ_F9") (pintype "power_in"))
      (node (ref "U1") (pin "G1") (pinfunction "VSSQ_G1") (pintype "power_in"))
      (node (ref "U1") (pin "G8") (pinfunction "VSS_G8") (pintype "power_in"))
      (node (ref "U1") (pin "G9") (pinfunction "VSSQ_G9") (pintype "power_in"))
      (node (ref "U1") (pin "J2") (pinfunction "VSS_J2") (pintype "power_in"))
      (node (ref "U1") (pin "J8") (pinfunction "VSS_J8") (pintype "power_in"))
      (node (ref "U1") (pin "M1") (pinfunction "VSS_M1") (pintype "power_in"))
      (node (ref "U1") (pin "M9") (pinfunction "VSS_M9") (pintype "power_in"))
      (node (ref "U1") (pin "P1") (pinfunction "VSS_P1") (pintype "power_in"))
      (node (ref "U1") (pin "P9") (pinfunction "VSS_P9") (pintype "power_in"))
      (node (ref "U1") (pin "T1") (pinfunction "VSS_T1") (pintype "power_in"))
      (node (ref "U1") (pin "T9") (pinfunction "VSS_T9") (pintype "power_in"))
      (node (ref "U2") (pin "A9") (pinfunction "VSS_A9") (pintype "power_in"))
      (node (ref "U2") (pin "B1") (pinfunction "VSSQ_B1") (pintype "power_in"))
      (node (ref "U2") (pin "B3") (pinfunction "VSS_B3") (pintype "power_in"))
      (node (ref "U2") (pin "B9") (pinfunction "VSSQ_B9") (pintype "power_in"))
      (node (ref "U2") (pin "D1") (pinfunction "VSSQ_D1") (pintype "power_in"))
      (node (ref "U2") (pin "D8") (pinfunction "VSSQ_D8") (pintype "power_in"))
      (node (ref "U2") (pin "E1") (pinfunction "VSS_E1") (pintype "power_in"))
      (node (ref "U2") (pin "E2") (pinfunction "VSSQ_E2") (pintype "power_in"))
      (node (ref "U2") (pin "E8") (pinfunction "VSSQ_E8") (pintype "power_in"))
      (node (ref "U2") (pin "F9") (pinfunction "VSSQ_F9") (pintype "power_in"))
      (node (ref "U2") (pin "G1") (pinfunction "VSSQ_G1") (pintype "power_in"))
      (node (ref "U2") (pin "G8") (pinfunction "VSS_G8") (pintype "power_in"))
      (node (ref "U2") (pin "G9") (pinfunction "VSSQ_G9") (pintype "power_in"))
      (node (ref "U2") (pin "J2") (pinfunction "VSS_J2") (pintype "power_in"))
      (node (ref "U2") (pin "J8") (pinfunction "VSS_J8") (pintype "power_in"))
      (node (ref "U2") (pin "M1") (pinfunction "VSS_M1") (pintype "power_in"))
      (node (ref "U2") (pin "M9") (pinfunction "VSS_M9") (pintype "power_in"))
      (node (ref "U2") (pin "P1") (pinfunction "VSS_P1") (pintype "power_in"))
      (node (ref "U2") (pin "P9") (pinfunction "VSS_P9") (pintype "power_in"))
      (node (ref "U2") (pin "T1") (pinfunction "VSS_T1") (pintype "power_in"))
      (node (ref "U2") (pin "T9") (pinfunction "VSS_T9") (pintype "power_in"))
    )
    (net (code "90") (name "Net-(C20-+)") (class "Default")
      (node (ref "C20") (pin "1") (pinfunction "+_1") (pintype "passive"))
      (node (ref "D5") (pin "1") (pinfunction "REFIN_1") (pintype "input"))
      (node (ref "R58") (pin "2") (pinfunction "-_2") (pintype "passive"))
      (node (ref "R59") (pin "2") (pinfunction "-_2") (pintype "passive"))
    )
    (net (code "91") (name "Net-(D2C-RZQ_0)") (class "Default")
      (node (ref "D2") (pin "AG17") (pinfunction "RZQ_0_AG17") (pintype "bidirectional"))
      (node (ref "R57") (pin "1") (pinfunction "+_1") (pintype "passive"))
    )
    (net (code "92") (name "Net-(D5-EN)") (class "Default")
      (node (ref "D5") (pin "7") (pinfunction "EN_7") (pintype "input"))
      (node (ref "R56") (pin "2") (pinfunction "-_2") (pintype "passive"))
    )
    (net (code "93") (name "Net-(D5-PGOOD)") (class "Default")
      (node (ref "D5") (pin "9") (pinfunction "PGOOD_9") (pintype "open_collector"))
      (node (ref "R55") (pin "2") (pinfunction "-_2") (pintype "passive"))
    )
    (net (code "94") (name "Net-(R47-+)") (class "Default")
      (node (ref "R47") (pin "1") (pinfunction "+_1") (pintype "passive"))
      (node (ref "U1") (pin "L8") (pinfunction "ZQ_L8") (pintype "input"))
    )
    (net (code "95") (name "Net-(R48-+)") (class "Default")
      (node (ref "R48") (pin "1") (pinfunction "+_1") (pintype "passive"))
      (node (ref "U2") (pin "L8") (pinfunction "ZQ_L8") (pintype "input"))
    )
    (net (code "96") (name "VCC1P5_DDR3") (class "Default")
      (node (ref "C19") (pin "1") (pinfunction "+_1") (pintype "passive"))
      (node (ref "D5") (pin "2") (pinfunction "VLDOIN_2") (pintype "power_in"))
      (node (ref "R49") (pin "1") (pinfunction "+_1") (pintype "passive"))
      (node (ref "R58") (pin "1") (pinfunction "+_1") (pintype "passive"))
      (node (ref "U1") (pin "A1") (pinfunction "VDDQ_A1") (pintype "power_in"))
      (node (ref "U1") (pin "A8") (pinfunction "VDDQ_A8") (pintype "power_in"))
      (node (ref "U1") (pin "B2") (pinfunction "VDD_B2") (pintype "power_in"))
      (node (ref "U1") (pin "C1") (pinfunction "VDDQ_C1") (pintype "power_in"))
      (node (ref "U1") (pin "C9") (pinfunction "VDDQ_C9") (pintype "power_in"))
      (node (ref "U1") (pin "D2") (pinfunction "VDDQ_D2") (pintype "power_in"))
      (node (ref "U1") (pin "D9") (pinfunction "VDD_D9") (pintype "power_in"))
      (node (ref "U1") (pin "E9") (pinfunction "VDDQ_E9") (pintype "power_in"))
      (node (ref "U1") (pin "F1") (pinfunction "VDDQ_F1") (pintype "power_in"))
      (node (ref "U1") (pin "G7") (pinfunction "VDD_G7") (pintype "power_in"))
      (node (ref "U1") (pin "H2") (pinfunction "VDDQ_H2") (pintype "power_in"))
      (node (ref "U1") (pin "H9") (pinfunction "VDDQ_H9") (pintype "power_in"))
      (node (ref "U1") (pin "K2") (pinfunction "VDD_K2") (pintype "power_in"))
      (node (ref "U1") (pin "K8") (pinfunction "VDD_K8") (pintype "power_in"))
      (node (ref "U1") (pin "N1") (pinfunction "VDD_N1") (pintype "power_in"))
      (node (ref "U1") (pin "N9") (pinfunction "VDD_N9") (pintype "power_in"))
      (node (ref "U1") (pin "R1") (pinfunction "VDD_R1") (pintype "power_in"))
      (node (ref "U1") (pin "R9") (pinfunction "VDD_R9") (pintype "power_in"))
      (node (ref "U2") (pin "A1") (pinfunction "VDDQ_A1") (pintype "power_in"))
      (node (ref "U2") (pin "A8") (pinfunction "VDDQ_A8") (pintype "power_in"))
      (node (ref "U2") (pin "B2") (pinfunction "VDD_B2") (pintype "power_in"))
      (node (ref "U2") (pin "C1") (pinfunction "VDDQ_C1") (pintype "power_in"))
      (node (ref "U2") (pin "C9") (pinfunction "VDDQ_C9") (pintype "power_in"))
      (node (ref "U2") (pin "D2") (pinfunction "VDDQ_D2") (pintype "power_in"))
      (node (ref "U2") (pin "D9") (pinfunction "VDD_D9") (pintype "power_in"))
      (node (ref "U2") (pin "E9") (pinfunction "VDDQ_E9") (pintype "power_in"))
      (node (ref "U2") (pin "F1") (pinfunction "VDDQ_F1") (pintype "power_in"))
      (node (ref "U2") (pin "G7") (pinfunction "VDD_G7") (pintype "power_in"))
      (node (ref "U2") (pin "H2") (pinfunction "VDDQ_H2") (pintype "power_in"))
      (node (ref "U2") (pin "H9") (pinfunction "VDDQ_H9") (pintype "power_in"))
      (node (ref "U2") (pin "K2") (pinfunction "VDD_K2") (pintype "power_in"))
      (node (ref "U2") (pin "K8") (pinfunction "VDD_K8") (pintype "power_in"))
      (node (ref "U2") (pin "N1") (pinfunction "VDD_N1") (pintype "power_in"))
      (node (ref "U2") (pin "N9") (pinfunction "VDD_N9") (pintype "power_in"))
      (node (ref "U2") (pin "R1") (pinfunction "VDD_R1") (pintype "power_in"))
      (node (ref "U2") (pin "R9") (pinfunction "VDD_R9") (pintype "power_in"))
    )
    (net (code "97") (name "VCC3P3") (class "Default")
      (node (ref "C16") (pin "1") (pinfunction "+_1") (pintype "passive"))
      (node (ref "D5") (pin "10") (pinfunction "VIN_10") (pintype "power_in"))
      (node (ref "R55") (pin "1") (pinfunction "+_1") (pintype "passive"))
      (node (ref "R56") (pin "1") (pinfunction "+_1") (pintype "passive"))
    )
    (net (code "98") (name "unconnected-(D2B-CLK1n-PadY16)") (class "Default")
      (node (ref "D2") (pin "Y16") (pinfunction "CLK1n_Y16") (pintype "bidirectional"))
    )
    (net (code "99") (name "unconnected-(D2B-DIFFIO_RX_B18n-PadAG11)") (class "Default")
      (node (ref "D2") (pin "AG11") (pinfunction "DIFFIO_RX_B18n_AG11") (pintype "bidirectional"))
    )
    (net (code "100") (name "unconnected-(D2B-DIFFIO_TX_B17n-PadAH9)") (class "Default")
      (node (ref "D2") (pin "AH9") (pinfunction "DIFFIO_TX_B17n_AH9") (pintype "bidirectional+no_connect"))
    )
    (net (code "101") (name "unconnected-(D2B-DIFFIO_TX_B17p-PadAG10)") (class "Default")
      (node (ref "D2") (pin "AG10") (pinfunction "DIFFIO_TX_B17p_AG10") (pintype "bidirectional+no_connect"))
    )
    (net (code "102") (name "unconnected-(D2B-DIFFIO_TX_B20n-PadAK3)") (class "Default")
      (node (ref "D2") (pin "AK3") (pinfunction "DIFFIO_TX_B20n_AK3") (pintype "bidirectional+no_connect"))
    )
    (net (code "103") (name "unconnected-(D2B-DIFFIO_TX_B20p-PadAK2)") (class "Default")
      (node (ref "D2") (pin "AK2") (pinfunction "DIFFIO_TX_B20p_AK2") (pintype "bidirectional+no_connect"))
    )
    (net (code "104") (name "unconnected-(D2B-DIFFIO_TX_B21n-PadAK4)") (class "Default")
      (node (ref "D2") (pin "AK4") (pinfunction "DIFFIO_TX_B21n_AK4") (pintype "bidirectional+no_connect"))
    )
    (net (code "105") (name "unconnected-(D2B-DIFFIO_TX_B21p-PadAJ4)") (class "Default")
      (node (ref "D2") (pin "AJ4") (pinfunction "DIFFIO_TX_B21p_AJ4") (pintype "bidirectional+no_connect"))
    )
    (net (code "106") (name "unconnected-(D2B-DIFFIO_TX_B24n-PadAK6)") (class "Default")
      (node (ref "D2") (pin "AK6") (pinfunction "DIFFIO_TX_B24n_AK6") (pintype "bidirectional+no_connect"))
    )
    (net (code "107") (name "unconnected-(D2B-DIFFIO_TX_B24p-PadAJ5)") (class "Default")
      (node (ref "D2") (pin "AJ5") (pinfunction "DIFFIO_TX_B24p_AJ5") (pintype "bidirectional+no_connect"))
    )
    (net (code "108") (name "unconnected-(D2B-IO-PadAC14)") (class "Default")
      (node (ref "D2") (pin "AC14") (pinfunction "IO_AC14") (pintype "bidirectional+no_connect"))
    )
    (net (code "109") (name "unconnected-(D2B-IO-PadAG13)") (class "Default")
      (node (ref "D2") (pin "AG13") (pinfunction "IO_AG13") (pintype "bidirectional+no_connect"))
    )
    (net (code "110") (name "unconnected-(D2C-CLK2n-PadAB17)") (class "Default")
      (node (ref "D2") (pin "AB17") (pinfunction "CLK2n_AB17") (pintype "bidirectional"))
    )
    (net (code "111") (name "unconnected-(D2C-CLK3n-PadAD17)") (class "Default")
      (node (ref "D2") (pin "AD17") (pinfunction "CLK3n_AD17") (pintype "bidirectional"))
    )
    (net (code "112") (name "unconnected-(D2C-CLK3p-PadAC18)") (class "Default")
      (node (ref "D2") (pin "AC18") (pinfunction "CLK3p_AC18") (pintype "bidirectional"))
    )
    (net (code "113") (name "unconnected-(D2C-DIFFIO_RX_B74n-PadAD21)") (class "Default")
      (node (ref "D2") (pin "AD21") (pinfunction "DIFFIO_RX_B74n_AD21") (pintype "bidirectional+no_connect"))
    )
    (net (code "114") (name "unconnected-(D2C-DIFFIO_RX_B74p-PadAD20)") (class "Default")
      (node (ref "D2") (pin "AD20") (pinfunction "DIFFIO_RX_B74p_AD20") (pintype "bidirectional+no_connect"))
    )
    (net (code "115") (name "unconnected-(D2C-DIFFIO_RX_B75n-PadAA20)") (class "Default")
      (node (ref "D2") (pin "AA20") (pinfunction "DIFFIO_RX_B75n_AA20") (pintype "bidirectional+no_connect"))
    )
    (net (code "116") (name "unconnected-(D2C-DIFFIO_RX_B75p-PadY19)") (class "Default")
      (node (ref "D2") (pin "Y19") (pinfunction "DIFFIO_RX_B75p_Y19") (pintype "bidirectional+no_connect"))
    )
    (net (code "117") (name "unconnected-(D2C-DIFFIO_RX_B78n-PadAC23)") (class "Default")
      (node (ref "D2") (pin "AC23") (pinfunction "DIFFIO_RX_B78n_AC23") (pintype "bidirectional+no_connect"))
    )
    (net (code "118") (name "unconnected-(D2C-DIFFIO_RX_B78p-PadAC22)") (class "Default")
      (node (ref "D2") (pin "AC22") (pinfunction "DIFFIO_RX_B78p_AC22") (pintype "bidirectional+no_connect"))
    )
    (net (code "119") (name "unconnected-(D2C-DIFFIO_TX_B80n-PadAE24)") (class "Default")
      (node (ref "D2") (pin "AE24") (pinfunction "DIFFIO_TX_B80n_AE24") (pintype "bidirectional+no_connect"))
    )
    (net (code "120") (name "unconnected-(D2C-DIFFIO_TX_B80p-PadAD24)") (class "Default")
      (node (ref "D2") (pin "AD24") (pinfunction "DIFFIO_TX_B80p_AD24") (pintype "bidirectional+no_connect"))
    )
    (net (code "121") (name "unconnected-(D2C-GND-PadAA19)") (class "Default")
      (node (ref "D2") (pin "AA19") (pinfunction "GND_AA19") (pintype "bidirectional"))
    )
    (net (code "122") (name "unconnected-(D2C-GND-PadAA21)") (class "Default")
      (node (ref "D2") (pin "AA21") (pinfunction "GND_AA21") (pintype "bidirectional"))
    )
    (net (code "123") (name "unconnected-(D2C-GND-PadAB21)") (class "Default")
      (node (ref "D2") (pin "AB21") (pinfunction "GND_AB21") (pintype "bidirectional"))
    )
    (net (code "124") (name "unconnected-(D2C-GND-PadAF26)") (class "Default")
      (node (ref "D2") (pin "AF26") (pinfunction "GND_AF26") (pintype "bidirectional"))
    )
    (net (code "125") (name "unconnected-(D2C-GND-PadAG26)") (class "Default")
      (node (ref "D2") (pin "AG26") (pinfunction "GND_AG26") (pintype "bidirectional"))
    )
    (net (code "126") (name "unconnected-(D2C-GND-PadAH19)") (class "Default")
      (node (ref "D2") (pin "AH19") (pinfunction "GND_AH19") (pintype "bidirectional"))
    )
    (net (code "127") (name "unconnected-(D2C-GND-PadAH22)") (class "Default")
      (node (ref "D2") (pin "AH22") (pinfunction "GND_AH22") (pintype "bidirectional"))
    )
    (net (code "128") (name "unconnected-(D2C-GND-PadAH25)") (class "Default")
      (node (ref "D2") (pin "AH25") (pinfunction "GND_AH25") (pintype "bidirectional"))
    )
    (net (code "129") (name "unconnected-(D2C-GND-PadAJ25)") (class "Default")
      (node (ref "D2") (pin "AJ25") (pinfunction "GND_AJ25") (pintype "bidirectional"))
    )
    (net (code "130") (name "unconnected-(D2C-GND-PadAJ26)") (class "Default")
      (node (ref "D2") (pin "AJ26") (pinfunction "GND_AJ26") (pintype "bidirectional"))
    )
    (net (code "131") (name "unconnected-(D2C-GND-PadAK29)") (class "Default")
      (node (ref "D2") (pin "AK29") (pinfunction "GND_AK29") (pintype "bidirectional"))
    )
    (net (code "132") (name "unconnected-(D2C-GND-PadV18)") (class "Default")
      (node (ref "D2") (pin "V18") (pinfunction "GND_V18") (pintype "bidirectional"))
    )
    (net (code "133") (name "unconnected-(D2C-GND-PadW19)") (class "Default")
      (node (ref "D2") (pin "W19") (pinfunction "GND_W19") (pintype "bidirectional"))
    )
    (net (code "134") (name "unconnected-(D2C-GND-PadY18)") (class "Default")
      (node (ref "D2") (pin "Y18") (pinfunction "GND_Y18") (pintype "bidirectional"))
    )
    (net (code "135") (name "unconnected-(D2C-IO-PadAF25)") (class "Default")
      (node (ref "D2") (pin "AF25") (pinfunction "IO_AF25") (pintype "bidirectional+no_connect"))
    )
    (net (code "136") (name "unconnected-(D2C-IO-PadAH27)") (class "Default")
      (node (ref "D2") (pin "AH27") (pinfunction "IO_AH27") (pintype "bidirectional+no_connect"))
    )
    (net (code "137") (name "unconnected-(D2C-IO-PadAJ19)") (class "Default")
      (node (ref "D2") (pin "AJ19") (pinfunction "IO_AJ19") (pintype "bidirectional+no_connect"))
    )
    (net (code "138") (name "unconnected-(D2C-IO-PadAK16)") (class "Default")
      (node (ref "D2") (pin "AK16") (pinfunction "IO_AK16") (pintype "bidirectional+no_connect"))
    )
    (net (code "139") (name "unconnected-(D2C-IO-PadAK28)") (class "Default")
      (node (ref "D2") (pin "AK28") (pinfunction "IO_AK28") (pintype "bidirectional+no_connect"))
    )
    (net (code "140") (name "unconnected-(U1C-NC-PadJ1)") (class "Default")
      (node (ref "U1") (pin "J1") (pinfunction "NC_J1") (pintype "passive"))
    )
    (net (code "141") (name "unconnected-(U1C-NC-PadJ9)") (class "Default")
      (node (ref "U1") (pin "J9") (pinfunction "NC_J9") (pintype "passive"))
    )
    (net (code "142") (name "unconnected-(U1C-NC-PadL1)") (class "Default")
      (node (ref "U1") (pin "L1") (pinfunction "NC_L1") (pintype "passive"))
    )
    (net (code "143") (name "unconnected-(U1C-NC-PadL9)") (class "Default")
      (node (ref "U1") (pin "L9") (pinfunction "NC_L9") (pintype "passive"))
    )
    (net (code "144") (name "unconnected-(U1C-NC-PadM7)") (class "Default")
      (node (ref "U1") (pin "M7") (pinfunction "NC_M7") (pintype "passive"))
    )
    (net (code "145") (name "unconnected-(U2C-NC-PadJ1)") (class "Default")
      (node (ref "U2") (pin "J1") (pinfunction "NC_J1") (pintype "passive"))
    )
    (net (code "146") (name "unconnected-(U2C-NC-PadJ9)") (class "Default")
      (node (ref "U2") (pin "J9") (pinfunction "NC_J9") (pintype "passive"))
    )
    (net (code "147") (name "unconnected-(U2C-NC-PadL1)") (class "Default")
      (node (ref "U2") (pin "L1") (pinfunction "NC_L1") (pintype "passive"))
    )
    (net (code "148") (name "unconnected-(U2C-NC-PadL9)") (class "Default")
      (node (ref "U2") (pin "L9") (pinfunction "NC_L9") (pintype "passive"))
    )
    (net (code "149") (name "unconnected-(U2C-NC-PadM7)") (class "Default")
      (node (ref "U2") (pin "M7") (pinfunction "NC_M7") (pintype "passive"))
    )
  )
)
